# LED_Slave_Board.net
KiCad netlist of a schematic drawn in EAGLE
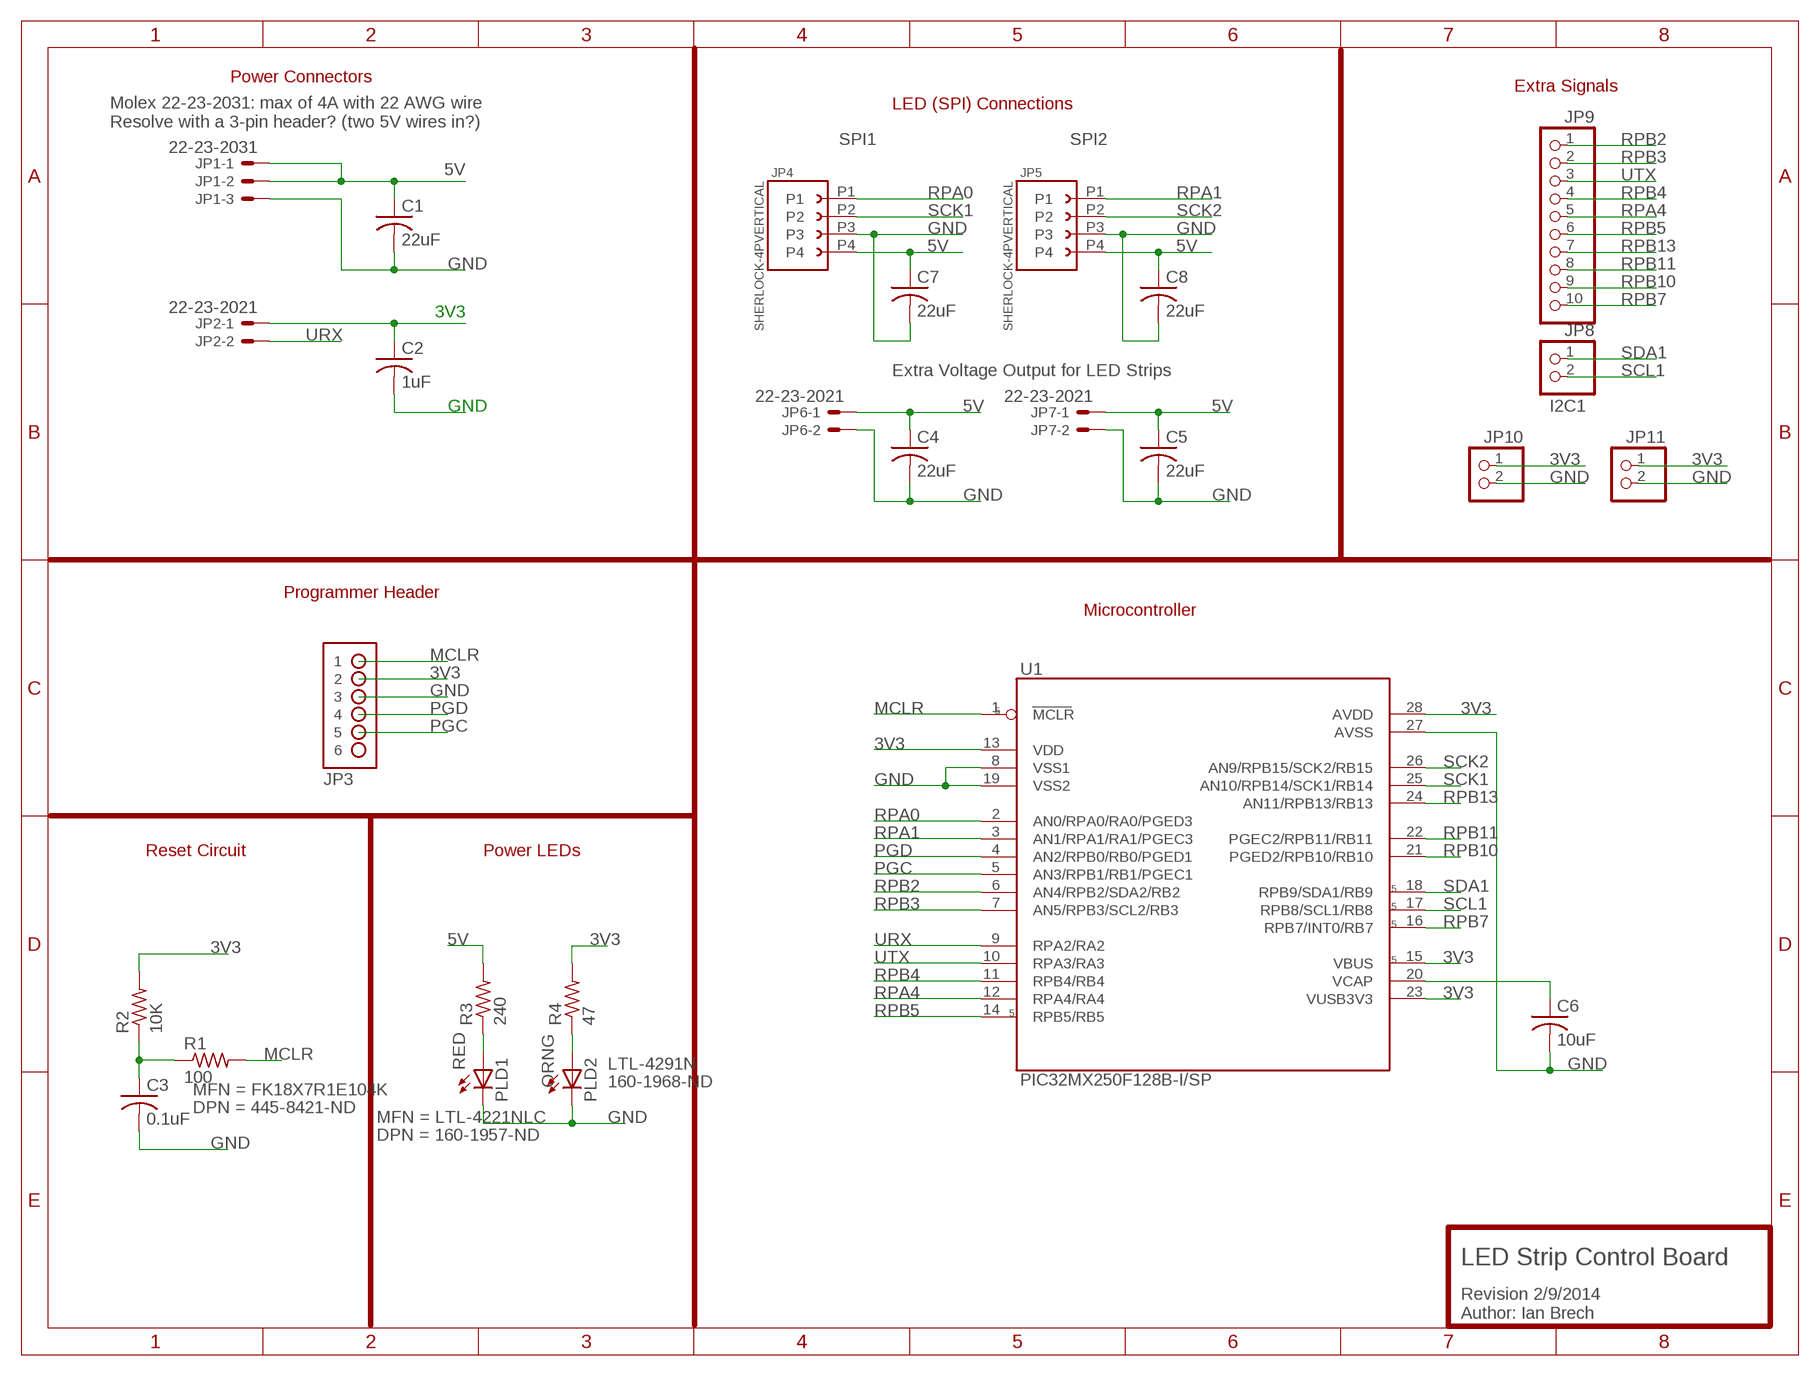
[diagram p0: schematic, sheet 1]

(export (version "E")
  (design (tool "Eeschema 10.0.6"))
  (components
    (comp (ref "C1")
      (value "22uF")
      (footprint "eagle-import:C050-045X075")
      (libsource (lib "eagle-import") (part "C-US050-045X075"))
    )
    (comp (ref "C2")
      (value "1uF")
      (footprint "eagle-import:C025-024X044")
      (libsource (lib "eagle-import") (part "C-US025-024X044"))
    )
    (comp (ref "C3")
      (value "0.1uF")
      (footprint "eagle-import:C025-040X050")
      (fields (field (name "DPN") "445-8421-ND") (field (name "MFN") "FK18X7R1E104K"))
      (libsource (lib "eagle-import") (part "C-US025-040X050"))
    )
    (comp (ref "C4")
      (value "22uF")
      (footprint "eagle-import:C050-045X075")
      (libsource (lib "eagle-import") (part "C-US050-045X075"))
    )
    (comp (ref "C5")
      (value "22uF")
      (footprint "eagle-import:C050-045X075")
      (libsource (lib "eagle-import") (part "C-US050-045X075"))
    )
    (comp (ref "C6")
      (value "10uF")
      (footprint "eagle-import:C025-040X050")
      (libsource (lib "eagle-import") (part "C-US025-040X050"))
    )
    (comp (ref "C7")
      (value "22uF")
      (footprint "eagle-import:C050-045X075")
      (libsource (lib "eagle-import") (part "C-US050-045X075"))
    )
    (comp (ref "C8")
      (value "22uF")
      (footprint "eagle-import:C050-045X075")
      (libsource (lib "eagle-import") (part "C-US050-045X075"))
    )
    (comp (ref "JP1")
      (value "22-23-2031")
      (footprint "eagle-import:22-23-2031")
      (fields (field (name "MF") "MOLEX"))
      (libsource (lib "eagle-import") (part "22-23-2031"))
    )
    (comp (ref "JP2")
      (value "22-23-2021")
      (footprint "eagle-import:22-23-2021")
      (fields (field (name "MF") "MOLEX"))
      (libsource (lib "eagle-import") (part "22-23-2021"))
    )
    (comp (ref "JP3")
      (value "HDR-1X6-OFFSET")
      (footprint "eagle-import:HDR-1X6_OFFSET")
      (libsource (lib "eagle-import") (part "HDR-1X6-OFFSET"))
    )
    (comp (ref "JP4")
      (value "SHERLOCK-4PVERTICAL")
      (footprint "eagle-import:35362-04__")
      (libsource (lib "eagle-import") (part "SHERLOCK-4PVERTICAL"))
    )
    (comp (ref "JP5")
      (value "SHERLOCK-4PVERTICAL")
      (footprint "eagle-import:35362-04__")
      (libsource (lib "eagle-import") (part "SHERLOCK-4PVERTICAL"))
    )
    (comp (ref "JP6")
      (value "22-23-2021")
      (footprint "eagle-import:22-23-2021")
      (fields (field (name "MF") "MOLEX"))
      (libsource (lib "eagle-import") (part "22-23-2021"))
    )
    (comp (ref "JP7")
      (value "22-23-2021")
      (footprint "eagle-import:22-23-2021")
      (fields (field (name "MF") "MOLEX"))
      (libsource (lib "eagle-import") (part "22-23-2021"))
    )
    (comp (ref "JP8")
      (value "PINHD-1X2")
      (footprint "eagle-import:1X02")
      (libsource (lib "eagle-import") (part "PINHD-1X2"))
    )
    (comp (ref "JP9")
      (value "PINHD-1X10")
      (footprint "eagle-import:1X10")
      (libsource (lib "eagle-import") (part "PINHD-1X10"))
    )
    (comp (ref "JP10")
      (value "PINHD-1X2")
      (footprint "eagle-import:1X02")
      (libsource (lib "eagle-import") (part "PINHD-1X2"))
    )
    (comp (ref "JP11")
      (value "PINHD-1X2")
      (footprint "eagle-import:1X02")
      (libsource (lib "eagle-import") (part "PINHD-1X2"))
    )
    (comp (ref "PLD1")
      (value "LED3MM")
      (footprint "eagle-import:LED3MM")
      (fields (field (name "DPN") "160-1957-ND") (field (name "MFN") "LTL-4221NLC"))
      (libsource (lib "eagle-import") (part "LED3MM"))
    )
    (comp (ref "PLD2")
      (value "LED3MM")
      (footprint "eagle-import:LED3MM")
      (fields (field (name "DPN") "160-1968-ND") (field (name "MFN") "LTL-4291N"))
      (libsource (lib "eagle-import") (part "LED3MM"))
    )
    (comp (ref "R1")
      (value "100")
      (footprint "eagle-import:0204_7")
      (libsource (lib "eagle-import") (part "R-US_0204/7"))
    )
    (comp (ref "R2")
      (value "10K")
      (footprint "eagle-import:0204_7")
      (libsource (lib "eagle-import") (part "R-US_0204/7"))
    )
    (comp (ref "R3")
      (value "240")
      (footprint "eagle-import:0204_7")
      (libsource (lib "eagle-import") (part "R-US_0204/7"))
    )
    (comp (ref "R4")
      (value "47")
      (footprint "eagle-import:0204_7")
      (libsource (lib "eagle-import") (part "R-US_0204/7"))
    )
    (comp (ref "U1")
      (value "PIC32MX250F128B-I/SP")
      (footprint "eagle-import:DIP254P762X508-28")
      (libsource (lib "eagle-import") (part "PIC32MX250F128B-I/SP"))
    )
  )
  (nets
    (net (code "1") (name "/3V3") (class "Default")
      (node (ref "C2") (pin "1") (pinfunction "1_1") (pintype "passive"))
      (node (ref "JP10") (pin "1") (pinfunction "1_1") (pintype "passive"))
      (node (ref "JP11") (pin "1") (pinfunction "1_1") (pintype "passive"))
      (node (ref "JP2") (pin "1") (pinfunction "S_1") (pintype "passive"))
      (node (ref "JP3") (pin "2") (pinfunction "2_2") (pintype "passive"))
      (node (ref "R2") (pin "2") (pinfunction "2_2") (pintype "passive"))
      (node (ref "R4") (pin "2") (pinfunction "2_2") (pintype "passive"))
      (node (ref "U1") (pin "13") (pinfunction "VDD_13") (pintype "bidirectional"))
      (node (ref "U1") (pin "15") (pinfunction "VBUS_15") (pintype "bidirectional"))
      (node (ref "U1") (pin "23") (pinfunction "VUSB3V3_23") (pintype "bidirectional"))
      (node (ref "U1") (pin "28") (pinfunction "AVDD_28") (pintype "bidirectional"))
    )
    (net (code "2") (name "/5V") (class "Default")
      (node (ref "C1") (pin "1") (pinfunction "1_1") (pintype "passive"))
      (node (ref "C4") (pin "1") (pinfunction "1_1") (pintype "passive"))
      (node (ref "C5") (pin "1") (pinfunction "1_1") (pintype "passive"))
      (node (ref "C7") (pin "1") (pinfunction "1_1") (pintype "passive"))
      (node (ref "C8") (pin "1") (pinfunction "1_1") (pintype "passive"))
      (node (ref "JP1") (pin "1") (pinfunction "S_1") (pintype "passive"))
      (node (ref "JP1") (pin "2") (pinfunction "S_2") (pintype "passive"))
      (node (ref "JP4") (pin "P4") (pinfunction "P4_P4") (pintype "bidirectional"))
      (node (ref "JP5") (pin "P4") (pinfunction "P4_P4") (pintype "bidirectional"))
      (node (ref "JP6") (pin "1") (pinfunction "S_1") (pintype "passive"))
      (node (ref "JP7") (pin "1") (pinfunction "S_1") (pintype "passive"))
      (node (ref "R3") (pin "2") (pinfunction "2_2") (pintype "passive"))
    )
    (net (code "3") (name "/GND") (class "Default")
      (node (ref "C1") (pin "2") (pinfunction "2_2") (pintype "passive"))
      (node (ref "C2") (pin "2") (pinfunction "2_2") (pintype "passive"))
      (node (ref "C3") (pin "2") (pinfunction "2_2") (pintype "passive"))
      (node (ref "C4") (pin "2") (pinfunction "2_2") (pintype "passive"))
      (node (ref "C5") (pin "2") (pinfunction "2_2") (pintype "passive"))
      (node (ref "C6") (pin "2") (pinfunction "2_2") (pintype "passive"))
      (node (ref "C7") (pin "2") (pinfunction "2_2") (pintype "passive"))
      (node (ref "C8") (pin "2") (pinfunction "2_2") (pintype "passive"))
      (node (ref "JP1") (pin "3") (pinfunction "S_3") (pintype "passive"))
      (node (ref "JP10") (pin "2") (pinfunction "2_2") (pintype "passive"))
      (node (ref "JP11") (pin "2") (pinfunction "2_2") (pintype "passive"))
      (node (ref "JP3") (pin "3") (pinfunction "3_3") (pintype "passive"))
      (node (ref "JP4") (pin "P3") (pinfunction "P3_P3") (pintype "bidirectional"))
      (node (ref "JP5") (pin "P3") (pinfunction "P3_P3") (pintype "bidirectional"))
      (node (ref "JP6") (pin "2") (pinfunction "S_2") (pintype "passive"))
      (node (ref "JP7") (pin "2") (pinfunction "S_2") (pintype "passive"))
      (node (ref "PLD1") (pin "K") (pinfunction "C_K") (pintype "passive"))
      (node (ref "PLD2") (pin "K") (pinfunction "C_K") (pintype "passive"))
      (node (ref "U1") (pin "19") (pinfunction "VSS2_19") (pintype "bidirectional"))
      (node (ref "U1") (pin "27") (pinfunction "AVSS_27") (pintype "bidirectional"))
      (node (ref "U1") (pin "8") (pinfunction "VSS1_8") (pintype "bidirectional"))
    )
    (net (code "4") (name "/MCLR") (class "Default")
      (node (ref "JP3") (pin "1") (pinfunction "1_1") (pintype "passive"))
      (node (ref "R1") (pin "2") (pinfunction "2_2") (pintype "passive"))
      (node (ref "U1") (pin "1") (pinfunction "MCLR_1") (pintype "bidirectional"))
    )
    (net (code "5") (name "/PGC") (class "Default")
      (node (ref "JP3") (pin "5") (pinfunction "5_5") (pintype "passive"))
      (node (ref "U1") (pin "5") (pinfunction "AN3/RPB1/RB1/PGEC1_5") (pintype "bidirectional"))
    )
    (net (code "6") (name "/PGD") (class "Default")
      (node (ref "JP3") (pin "4") (pinfunction "4_4") (pintype "passive"))
      (node (ref "U1") (pin "4") (pinfunction "AN2/RPB0/RB0/PGED1_4") (pintype "bidirectional"))
    )
    (net (code "7") (name "/RPA0") (class "Default")
      (node (ref "JP4") (pin "P1") (pinfunction "P1_P1") (pintype "bidirectional"))
      (node (ref "U1") (pin "2") (pinfunction "AN0/RPA0/RA0/PGED3_2") (pintype "bidirectional"))
    )
    (net (code "8") (name "/RPA1") (class "Default")
      (node (ref "JP5") (pin "P1") (pinfunction "P1_P1") (pintype "bidirectional"))
      (node (ref "U1") (pin "3") (pinfunction "AN1/RPA1/RA1/PGEC3_3") (pintype "bidirectional"))
    )
    (net (code "9") (name "/RPA4") (class "Default")
      (node (ref "JP9") (pin "5") (pinfunction "5_5") (pintype "passive"))
      (node (ref "U1") (pin "12") (pinfunction "RPA4/RA4_12") (pintype "bidirectional"))
    )
    (net (code "10") (name "/RPB2") (class "Default")
      (node (ref "JP9") (pin "1") (pinfunction "1_1") (pintype "passive"))
      (node (ref "U1") (pin "6") (pinfunction "AN4/RPB2/SDA2/RB2_6") (pintype "bidirectional"))
    )
    (net (code "11") (name "/RPB3") (class "Default")
      (node (ref "JP9") (pin "2") (pinfunction "2_2") (pintype "passive"))
      (node (ref "U1") (pin "7") (pinfunction "AN5/RPB3/SCL2/RB3_7") (pintype "bidirectional"))
    )
    (net (code "12") (name "/RPB4") (class "Default")
      (node (ref "JP9") (pin "4") (pinfunction "4_4") (pintype "passive"))
      (node (ref "U1") (pin "11") (pinfunction "RPB4/RB4_11") (pintype "bidirectional"))
    )
    (net (code "13") (name "/RPB5") (class "Default")
      (node (ref "JP9") (pin "6") (pinfunction "6_6") (pintype "passive"))
      (node (ref "U1") (pin "14") (pinfunction "RPB5/RB5_14") (pintype "bidirectional"))
    )
    (net (code "14") (name "/RPB7") (class "Default")
      (node (ref "JP9") (pin "10") (pinfunction "10_10") (pintype "passive"))
      (node (ref "U1") (pin "16") (pinfunction "RPB7/INT0/RB7_16") (pintype "bidirectional"))
    )
    (net (code "15") (name "/RPB10") (class "Default")
      (node (ref "JP9") (pin "9") (pinfunction "9_9") (pintype "passive"))
      (node (ref "U1") (pin "21") (pinfunction "PGED2/RPB10/RB10_21") (pintype "bidirectional"))
    )
    (net (code "16") (name "/RPB11") (class "Default")
      (node (ref "JP9") (pin "8") (pinfunction "8_8") (pintype "passive"))
      (node (ref "U1") (pin "22") (pinfunction "PGEC2/RPB11/RB11_22") (pintype "bidirectional"))
    )
    (net (code "17") (name "/RPB13") (class "Default")
      (node (ref "JP9") (pin "7") (pinfunction "7_7") (pintype "passive"))
      (node (ref "U1") (pin "24") (pinfunction "AN11/RPB13/RB13_24") (pintype "bidirectional"))
    )
    (net (code "18") (name "/SCK1") (class "Default")
      (node (ref "JP4") (pin "P2") (pinfunction "P2_P2") (pintype "bidirectional"))
      (node (ref "U1") (pin "25") (pinfunction "AN10/RPB14/SCK1/RB14_25") (pintype "bidirectional"))
    )
    (net (code "19") (name "/SCK2") (class "Default")
      (node (ref "JP5") (pin "P2") (pinfunction "P2_P2") (pintype "bidirectional"))
      (node (ref "U1") (pin "26") (pinfunction "AN9/RPB15/SCK2/RB15_26") (pintype "bidirectional"))
    )
    (net (code "20") (name "/SCL1") (class "Default")
      (node (ref "JP8") (pin "2") (pinfunction "2_2") (pintype "passive"))
      (node (ref "U1") (pin "17") (pinfunction "RPB8/SCL1/RB8_17") (pintype "bidirectional"))
    )
    (net (code "21") (name "/SDA1") (class "Default")
      (node (ref "JP8") (pin "1") (pinfunction "1_1") (pintype "passive"))
      (node (ref "U1") (pin "18") (pinfunction "RPB9/SDA1/RB9_18") (pintype "bidirectional"))
    )
    (net (code "22") (name "/URX") (class "Default")
      (node (ref "JP2") (pin "2") (pinfunction "S_2") (pintype "passive"))
      (node (ref "U1") (pin "9") (pinfunction "RPA2/RA2_9") (pintype "bidirectional"))
    )
    (net (code "23") (name "/UTX") (class "Default")
      (node (ref "JP9") (pin "3") (pinfunction "3_3") (pintype "passive"))
      (node (ref "U1") (pin "10") (pinfunction "RPA3/RA3_10") (pintype "bidirectional"))
    )
    (net (code "24") (name "Net-(C3-Pad1)") (class "Default")
      (node (ref "C3") (pin "1") (pinfunction "1_1") (pintype "passive"))
      (node (ref "R1") (pin "1") (pinfunction "1_1") (pintype "passive"))
      (node (ref "R2") (pin "1") (pinfunction "1_1") (pintype "passive"))
    )
    (net (code "25") (name "Net-(PLD1-PadA)") (class "Default")
      (node (ref "PLD1") (pin "A") (pinfunction "A_A") (pintype "passive"))
      (node (ref "R3") (pin "1") (pinfunction "1_1") (pintype "passive"))
    )
    (net (code "26") (name "Net-(PLD2-PadA)") (class "Default")
      (node (ref "PLD2") (pin "A") (pinfunction "A_A") (pintype "passive"))
      (node (ref "R4") (pin "1") (pinfunction "1_1") (pintype "passive"))
    )
    (net (code "27") (name "Net-(U1-VCAP)") (class "Default")
      (node (ref "C6") (pin "1") (pinfunction "1_1") (pintype "passive"))
      (node (ref "U1") (pin "20") (pinfunction "VCAP_20") (pintype "bidirectional"))
    )
    (net (code "28") (name "unconnected-(JP3-Pad6)") (class "Default")
      (node (ref "JP3") (pin "6") (pinfunction "6_6") (pintype "passive"))
    )
  )
)
